# QCopterFC_PWM_Sch.net
KiCad netlist of a schematic drawn in Altium Designer
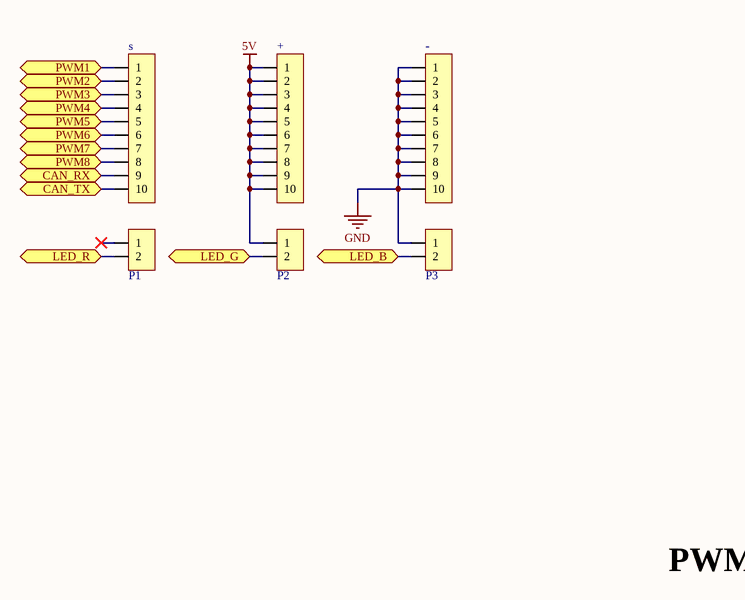
[diagram p0: QCopterFC_PWM_Sch.SchDoc]

(export (version "E")
  (design (tool "Eeschema 10.0.6"))
  (components
    (comp (ref "+")
      (value "HDR1X10_180_2.54")
      (footprint "PCB_Connector:HDR1X10_180_2.54")
      (description "Header")
      (libsource (lib "SCH_Connector") (part "HDR1X10_180_2.54"))
    )
    (comp (ref "-")
      (value "HDR1X10_180_2.54")
      (footprint "PCB_Connector:HDR1X10_180_2.54")
      (description "Header")
      (libsource (lib "SCH_Connector") (part "HDR1X10_180_2.54"))
    )
    (comp (ref "P1")
      (value "HDR1X2_180_2.54")
      (footprint "PCB_Connector:HDR1X2_180_2.54")
      (description "Header")
      (libsource (lib "SCH_Connector") (part "HDR1X2_180_2.54"))
    )
    (comp (ref "P2")
      (value "HDR1X2_180_2.54")
      (footprint "PCB_Connector:HDR1X2_180_2.54")
      (description "Header")
      (libsource (lib "SCH_Connector") (part "HDR1X2_180_2.54"))
    )
    (comp (ref "P3")
      (value "HDR1X2_180_2.54")
      (footprint "PCB_Connector:HDR1X2_180_2.54")
      (description "Header")
      (libsource (lib "SCH_Connector") (part "HDR1X2_180_2.54"))
    )
    (comp (ref "s")
      (value "HDR1X10_180_2.54")
      (footprint "PCB_Connector:HDR1X10_180_2.54")
      (description "Header")
      (libsource (lib "SCH_Connector") (part "HDR1X10_180_2.54"))
    )
  )
  (nets
    (net (code "1") (name "/CAN_RX") (class "Default")
      (node (ref "s") (pin "9") (pinfunction "9_9") (pintype "passive"))
    )
    (net (code "2") (name "/CAN_TX") (class "Default")
      (node (ref "s") (pin "10") (pinfunction "10_10") (pintype "passive"))
    )
    (net (code "3") (name "/LED_B") (class "Default")
      (node (ref "P3") (pin "2") (pinfunction "2_2") (pintype "passive"))
    )
    (net (code "4") (name "/LED_G") (class "Default")
      (node (ref "P2") (pin "2") (pinfunction "2_2") (pintype "passive"))
    )
    (net (code "5") (name "/LED_R") (class "Default")
      (node (ref "P1") (pin "2") (pinfunction "2_2") (pintype "passive"))
    )
    (net (code "6") (name "/PWM1") (class "Default")
      (node (ref "s") (pin "1") (pinfunction "1_1") (pintype "passive"))
    )
    (net (code "7") (name "/PWM2") (class "Default")
      (node (ref "s") (pin "2") (pinfunction "2_2") (pintype "passive"))
    )
    (net (code "8") (name "/PWM3") (class "Default")
      (node (ref "s") (pin "3") (pinfunction "3_3") (pintype "passive"))
    )
    (net (code "9") (name "/PWM4") (class "Default")
      (node (ref "s") (pin "4") (pinfunction "4_4") (pintype "passive"))
    )
    (net (code "10") (name "/PWM5") (class "Default")
      (node (ref "s") (pin "5") (pinfunction "5_5") (pintype "passive"))
    )
    (net (code "11") (name "/PWM6") (class "Default")
      (node (ref "s") (pin "6") (pinfunction "6_6") (pintype "passive"))
    )
    (net (code "12") (name "/PWM7") (class "Default")
      (node (ref "s") (pin "7") (pinfunction "7_7") (pintype "passive"))
    )
    (net (code "13") (name "/PWM8") (class "Default")
      (node (ref "s") (pin "8") (pinfunction "8_8") (pintype "passive"))
    )
    (net (code "14") (name "5V") (class "Default")
      (node (ref "+") (pin "1") (pinfunction "1_1") (pintype "passive"))
      (node (ref "+") (pin "10") (pinfunction "10_10") (pintype "passive"))
      (node (ref "+") (pin "2") (pinfunction "2_2") (pintype "passive"))
      (node (ref "+") (pin "3") (pinfunction "3_3") (pintype "passive"))
      (node (ref "+") (pin "4") (pinfunction "4_4") (pintype "passive"))
      (node (ref "+") (pin "5") (pinfunction "5_5") (pintype "passive"))
      (node (ref "+") (pin "6") (pinfunction "6_6") (pintype "passive"))
      (node (ref "+") (pin "7") (pinfunction "7_7") (pintype "passive"))
      (node (ref "+") (pin "8") (pinfunction "8_8") (pintype "passive"))
      (node (ref "+") (pin "9") (pinfunction "9_9") (pintype "passive"))
      (node (ref "P2") (pin "1") (pinfunction "1_1") (pintype "passive"))
    )
    (net (code "15") (name "GND") (class "Default")
      (node (ref "-") (pin "1") (pinfunction "1_1") (pintype "passive"))
      (node (ref "-") (pin "10") (pinfunction "10_10") (pintype "passive"))
      (node (ref "-") (pin "2") (pinfunction "2_2") (pintype "passive"))
      (node (ref "-") (pin "3") (pinfunction "3_3") (pintype "passive"))
      (node (ref "-") (pin "4") (pinfunction "4_4") (pintype "passive"))
      (node (ref "-") (pin "5") (pinfunction "5_5") (pintype "passive"))
      (node (ref "-") (pin "6") (pinfunction "6_6") (pintype "passive"))
      (node (ref "-") (pin "7") (pinfunction "7_7") (pintype "passive"))
      (node (ref "-") (pin "8") (pinfunction "8_8") (pintype "passive"))
      (node (ref "-") (pin "9") (pinfunction "9_9") (pintype "passive"))
      (node (ref "P3") (pin "1") (pinfunction "1_1") (pintype "passive"))
    )
    (net (code "16") (name "unconnected-(P1-Pad1)") (class "Default")
      (node (ref "P1") (pin "1") (pinfunction "1_1") (pintype "passive+no_connect"))
    )
  )
)
